# P16-Connector.net
KiCad netlist of a schematic drawn in Altium Designer
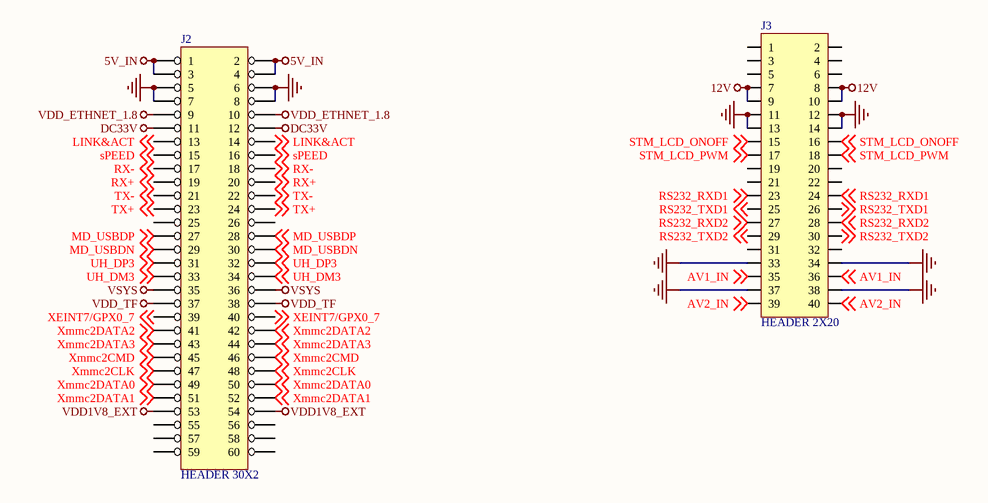
[diagram p0: P16-Connector.SchDoc]

(export (version "E")
  (design (tool "Eeschema 10.0.6"))
  (components
    (comp (ref "J2")
      (value "HEADER 30X2")
      (footprint "HD2X30-2.00")
      (libsource (lib "Connector Class") (part "HEADER 30X2"))
    )
    (comp (ref "J3")
      (value "HEADER 2X20")
      (footprint "HD2X20-2.00")
      (libsource (lib "Connector Class") (part "HEADER 2X20"))
    )
  )
  (nets
    (net (code "1") (name "5V_IN") (class "Default")
      (node (ref "J2") (pin "1") (pinfunction "1_1") (pintype "passive"))
      (node (ref "J2") (pin "2") (pinfunction "2_2") (pintype "passive"))
      (node (ref "J2") (pin "3") (pinfunction "3_3") (pintype "passive"))
      (node (ref "J2") (pin "4") (pinfunction "4_4") (pintype "passive"))
    )
    (net (code "2") (name "12V") (class "Default")
      (node (ref "J3") (pin "10") (pinfunction "10_10") (pintype "passive"))
      (node (ref "J3") (pin "7") (pinfunction "7_7") (pintype "passive"))
      (node (ref "J3") (pin "8") (pinfunction "8_8") (pintype "passive"))
      (node (ref "J3") (pin "9") (pinfunction "9_9") (pintype "passive"))
    )
    (net (code "3") (name "AV1_IN") (class "Default")
      (node (ref "J3") (pin "35") (pinfunction "35_35") (pintype "passive"))
      (node (ref "J3") (pin "36") (pinfunction "36_36") (pintype "passive"))
    )
    (net (code "4") (name "AV2_IN") (class "Default")
      (node (ref "J3") (pin "39") (pinfunction "39_39") (pintype "passive"))
      (node (ref "J3") (pin "40") (pinfunction "40_40") (pintype "passive"))
    )
    (net (code "5") (name "DC33V") (class "Default")
      (node (ref "J2") (pin "11") (pinfunction "11_11") (pintype "passive"))
      (node (ref "J2") (pin "12") (pinfunction "12_12") (pintype "passive"))
    )
    (net (code "6") (name "GND") (class "Default")
      (node (ref "J2") (pin "5") (pinfunction "5_5") (pintype "passive"))
      (node (ref "J2") (pin "6") (pinfunction "6_6") (pintype "passive"))
      (node (ref "J2") (pin "7") (pinfunction "7_7") (pintype "passive"))
      (node (ref "J2") (pin "8") (pinfunction "8_8") (pintype "passive"))
      (node (ref "J3") (pin "11") (pinfunction "11_11") (pintype "passive"))
      (node (ref "J3") (pin "12") (pinfunction "12_12") (pintype "passive"))
      (node (ref "J3") (pin "13") (pinfunction "13_13") (pintype "passive"))
      (node (ref "J3") (pin "14") (pinfunction "14_14") (pintype "passive"))
      (node (ref "J3") (pin "33") (pinfunction "33_33") (pintype "passive"))
      (node (ref "J3") (pin "34") (pinfunction "34_34") (pintype "passive"))
      (node (ref "J3") (pin "37") (pinfunction "37_37") (pintype "passive"))
      (node (ref "J3") (pin "38") (pinfunction "38_38") (pintype "passive"))
    )
    (net (code "7") (name "LINK&ACT") (class "Default")
      (node (ref "J2") (pin "13") (pinfunction "13_13") (pintype "passive"))
      (node (ref "J2") (pin "14") (pinfunction "14_14") (pintype "passive"))
    )
    (net (code "8") (name "MD_USBDN") (class "Default")
      (node (ref "J2") (pin "29") (pinfunction "29_29") (pintype "passive"))
      (node (ref "J2") (pin "30") (pinfunction "30_30") (pintype "passive"))
    )
    (net (code "9") (name "MD_USBDP") (class "Default")
      (node (ref "J2") (pin "27") (pinfunction "27_27") (pintype "passive"))
      (node (ref "J2") (pin "28") (pinfunction "28_28") (pintype "passive"))
    )
    (net (code "10") (name "RS232_RXD1") (class "Default")
      (node (ref "J3") (pin "23") (pinfunction "23_23") (pintype "passive"))
      (node (ref "J3") (pin "24") (pinfunction "24_24") (pintype "passive"))
    )
    (net (code "11") (name "RS232_RXD2") (class "Default")
      (node (ref "J3") (pin "27") (pinfunction "27_27") (pintype "passive"))
      (node (ref "J3") (pin "28") (pinfunction "28_28") (pintype "passive"))
    )
    (net (code "12") (name "RS232_TXD1") (class "Default")
      (node (ref "J3") (pin "25") (pinfunction "25_25") (pintype "passive"))
      (node (ref "J3") (pin "26") (pinfunction "26_26") (pintype "passive"))
    )
    (net (code "13") (name "RS232_TXD2") (class "Default")
      (node (ref "J3") (pin "29") (pinfunction "29_29") (pintype "passive"))
      (node (ref "J3") (pin "30") (pinfunction "30_30") (pintype "passive"))
    )
    (net (code "14") (name "RX+") (class "Default")
      (node (ref "J2") (pin "19") (pinfunction "19_19") (pintype "passive"))
      (node (ref "J2") (pin "20") (pinfunction "20_20") (pintype "passive"))
    )
    (net (code "15") (name "RX-") (class "Default")
      (node (ref "J2") (pin "17") (pinfunction "17_17") (pintype "passive"))
      (node (ref "J2") (pin "18") (pinfunction "18_18") (pintype "passive"))
    )
    (net (code "16") (name "STM_LCD_ONOFF") (class "Default")
      (node (ref "J3") (pin "15") (pinfunction "15_15") (pintype "passive"))
      (node (ref "J3") (pin "16") (pinfunction "16_16") (pintype "passive"))
    )
    (net (code "17") (name "STM_LCD_PWM") (class "Default")
      (node (ref "J3") (pin "17") (pinfunction "17_17") (pintype "passive"))
      (node (ref "J3") (pin "18") (pinfunction "18_18") (pintype "passive"))
    )
    (net (code "18") (name "TX+") (class "Default")
      (node (ref "J2") (pin "23") (pinfunction "23_23") (pintype "passive"))
      (node (ref "J2") (pin "24") (pinfunction "24_24") (pintype "passive"))
    )
    (net (code "19") (name "TX-") (class "Default")
      (node (ref "J2") (pin "21") (pinfunction "21_21") (pintype "passive"))
      (node (ref "J2") (pin "22") (pinfunction "22_22") (pintype "passive"))
    )
    (net (code "20") (name "UH_DM3") (class "Default")
      (node (ref "J2") (pin "33") (pinfunction "33_33") (pintype "passive"))
      (node (ref "J2") (pin "34") (pinfunction "34_34") (pintype "passive"))
    )
    (net (code "21") (name "UH_DP3") (class "Default")
      (node (ref "J2") (pin "31") (pinfunction "31_31") (pintype "passive"))
      (node (ref "J2") (pin "32") (pinfunction "32_32") (pintype "passive"))
    )
    (net (code "22") (name "VDD1V8_EXT") (class "Default")
      (node (ref "J2") (pin "53") (pinfunction "53_53") (pintype "passive"))
      (node (ref "J2") (pin "54") (pinfunction "54_54") (pintype "passive"))
    )
    (net (code "23") (name "VDD_ETHNET_1.8") (class "Default")
      (node (ref "J2") (pin "10") (pinfunction "10_10") (pintype "passive"))
      (node (ref "J2") (pin "9") (pinfunction "9_9") (pintype "passive"))
    )
    (net (code "24") (name "VDD_TF") (class "Default")
      (node (ref "J2") (pin "37") (pinfunction "37_37") (pintype "passive"))
      (node (ref "J2") (pin "38") (pinfunction "38_38") (pintype "passive"))
    )
    (net (code "25") (name "VSYS") (class "Default")
      (node (ref "J2") (pin "35") (pinfunction "35_35") (pintype "passive"))
      (node (ref "J2") (pin "36") (pinfunction "36_36") (pintype "passive"))
    )
    (net (code "26") (name "XEINT7{slash}GPX0_7") (class "Default")
      (node (ref "J2") (pin "39") (pinfunction "39_39") (pintype "passive"))
      (node (ref "J2") (pin "40") (pinfunction "40_40") (pintype "passive"))
    )
    (net (code "27") (name "Xmmc2CLK") (class "Default")
      (node (ref "J2") (pin "47") (pinfunction "47_47") (pintype "passive"))
      (node (ref "J2") (pin "48") (pinfunction "48_48") (pintype "passive"))
    )
    (net (code "28") (name "Xmmc2CMD") (class "Default")
      (node (ref "J2") (pin "45") (pinfunction "45_45") (pintype "passive"))
      (node (ref "J2") (pin "46") (pinfunction "46_46") (pintype "passive"))
    )
    (net (code "29") (name "Xmmc2DATA0") (class "Default")
      (node (ref "J2") (pin "49") (pinfunction "49_49") (pintype "passive"))
      (node (ref "J2") (pin "50") (pinfunction "50_50") (pintype "passive"))
    )
    (net (code "30") (name "Xmmc2DATA1") (class "Default")
      (node (ref "J2") (pin "51") (pinfunction "51_51") (pintype "passive"))
      (node (ref "J2") (pin "52") (pinfunction "52_52") (pintype "passive"))
    )
    (net (code "31") (name "Xmmc2DATA2") (class "Default")
      (node (ref "J2") (pin "41") (pinfunction "41_41") (pintype "passive"))
      (node (ref "J2") (pin "42") (pinfunction "42_42") (pintype "passive"))
    )
    (net (code "32") (name "Xmmc2DATA3") (class "Default")
      (node (ref "J2") (pin "43") (pinfunction "43_43") (pintype "passive"))
      (node (ref "J2") (pin "44") (pinfunction "44_44") (pintype "passive"))
    )
    (net (code "33") (name "sPEED") (class "Default")
      (node (ref "J2") (pin "15") (pinfunction "15_15") (pintype "passive"))
      (node (ref "J2") (pin "16") (pinfunction "16_16") (pintype "passive"))
    )
    (net (code "34") (name "unconnected-(J2-Pad25)") (class "Default")
      (node (ref "J2") (pin "25") (pinfunction "25_25") (pintype "passive"))
    )
    (net (code "35") (name "unconnected-(J2-Pad26)") (class "Default")
      (node (ref "J2") (pin "26") (pinfunction "26_26") (pintype "passive"))
    )
    (net (code "36") (name "unconnected-(J2-Pad55)") (class "Default")
      (node (ref "J2") (pin "55") (pinfunction "55_55") (pintype "passive"))
    )
    (net (code "37") (name "unconnected-(J2-Pad56)") (class "Default")
      (node (ref "J2") (pin "56") (pinfunction "56_56") (pintype "passive"))
    )
    (net (code "38") (name "unconnected-(J2-Pad57)") (class "Default")
      (node (ref "J2") (pin "57") (pinfunction "57_57") (pintype "passive"))
    )
    (net (code "39") (name "unconnected-(J2-Pad58)") (class "Default")
      (node (ref "J2") (pin "58") (pinfunction "58_58") (pintype "passive"))
    )
    (net (code "40") (name "unconnected-(J2-Pad59)") (class "Default")
      (node (ref "J2") (pin "59") (pinfunction "59_59") (pintype "passive"))
    )
    (net (code "41") (name "unconnected-(J2-Pad60)") (class "Default")
      (node (ref "J2") (pin "60") (pinfunction "60_60") (pintype "passive"))
    )
    (net (code "42") (name "unconnected-(J3-Pad1)") (class "Default")
      (node (ref "J3") (pin "1") (pinfunction "1_1") (pintype "passive"))
    )
    (net (code "43") (name "unconnected-(J3-Pad2)") (class "Default")
      (node (ref "J3") (pin "2") (pinfunction "2_2") (pintype "passive"))
    )
    (net (code "44") (name "unconnected-(J3-Pad3)") (class "Default")
      (node (ref "J3") (pin "3") (pinfunction "3_3") (pintype "passive"))
    )
    (net (code "45") (name "unconnected-(J3-Pad4)") (class "Default")
      (node (ref "J3") (pin "4") (pinfunction "4_4") (pintype "passive"))
    )
    (net (code "46") (name "unconnected-(J3-Pad5)") (class "Default")
      (node (ref "J3") (pin "5") (pinfunction "5_5") (pintype "passive"))
    )
    (net (code "47") (name "unconnected-(J3-Pad6)") (class "Default")
      (node (ref "J3") (pin "6") (pinfunction "6_6") (pintype "passive"))
    )
    (net (code "48") (name "unconnected-(J3-Pad19)") (class "Default")
      (node (ref "J3") (pin "19") (pinfunction "19_19") (pintype "passive"))
    )
    (net (code "49") (name "unconnected-(J3-Pad20)") (class "Default")
      (node (ref "J3") (pin "20") (pinfunction "20_20") (pintype "passive"))
    )
    (net (code "50") (name "unconnected-(J3-Pad21)") (class "Default")
      (node (ref "J3") (pin "21") (pinfunction "21_21") (pintype "passive"))
    )
    (net (code "51") (name "unconnected-(J3-Pad22)") (class "Default")
      (node (ref "J3") (pin "22") (pinfunction "22_22") (pintype "passive"))
    )
    (net (code "52") (name "unconnected-(J3-Pad31)") (class "Default")
      (node (ref "J3") (pin "31") (pinfunction "31_31") (pintype "passive"))
    )
    (net (code "53") (name "unconnected-(J3-Pad32)") (class "Default")
      (node (ref "J3") (pin "32") (pinfunction "32_32") (pintype "passive"))
    )
  )
)
